# openSX70-dongle_v3-9.net
KiCad netlist of a schematic drawn in EAGLE
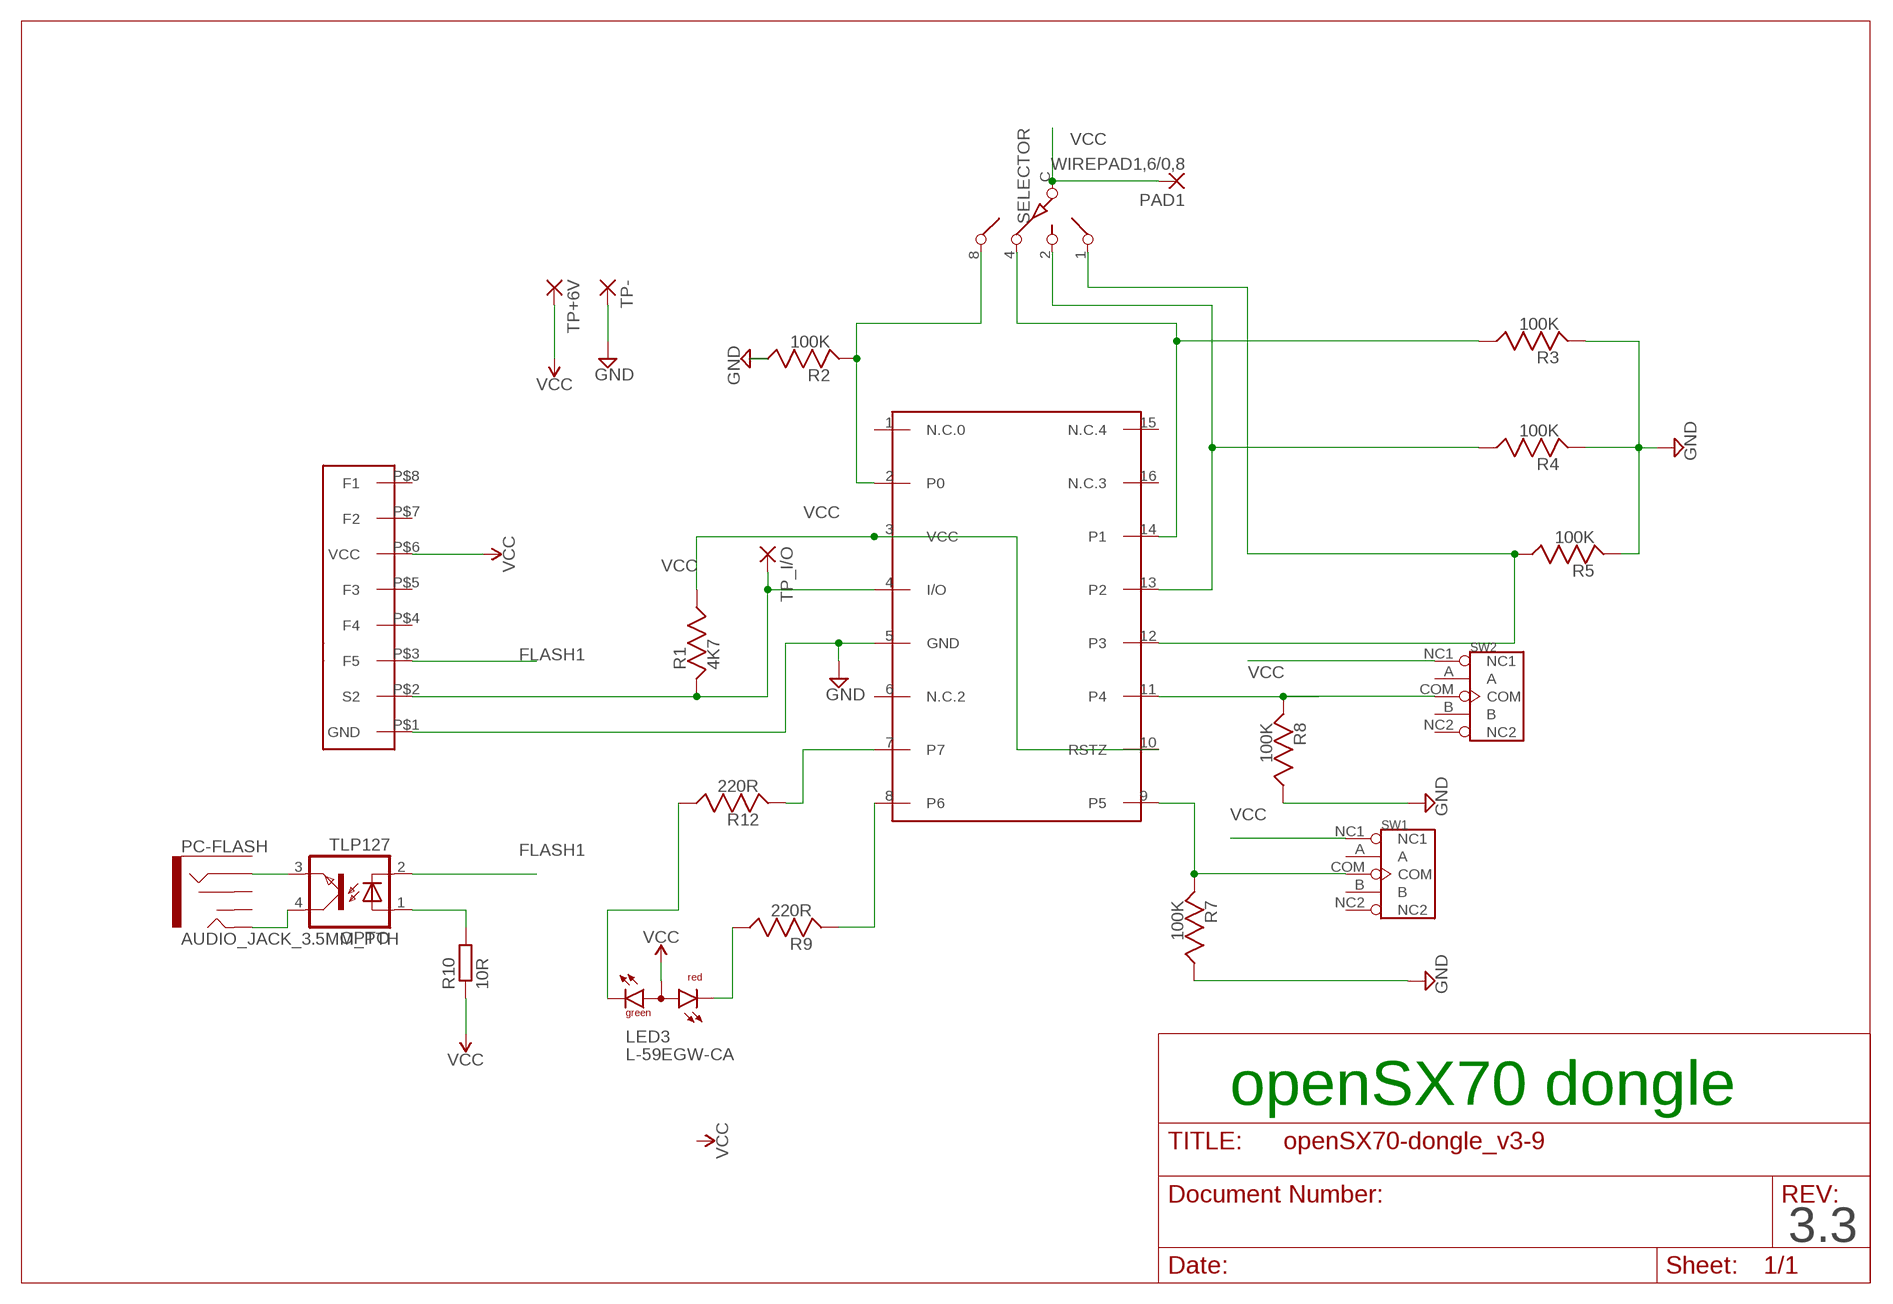
[diagram p0: schematic, sheet 1]

(export (version "E")
  (design (tool "Eeschema 10.0.6"))
  (components
    (comp (ref "DS2408")
      (value "DS2408")
      (footprint "eagle-import:SO16")
      (libsource (lib "eagle-import") (part "DS2408"))
    )
    (comp (ref "LED3")
      (value "L-59EGW-CA")
      (footprint "eagle-import:L-59EGW-CA")
      (libsource (lib "eagle-import") (part "L-59EGW-CA"))
    )
    (comp (ref "OPTO")
      (value "TLP127")
      (footprint "eagle-import:SO-4")
      (libsource (lib "eagle-import") (part "TLP127"))
    )
    (comp (ref "PAD1")
      (value "WIREPAD1,6/0,8")
      (footprint "eagle-import:1,6_0,8")
      (libsource (lib "eagle-import") (part "WIREPAD1,6/0,8"))
    )
    (comp (ref "PC-FLASH")
      (value "AUDIO_JACK_3.5MM_PTH")
      (footprint "eagle-import:AUDIO-JACK")
      (libsource (lib "eagle-import") (part "AUDIO_JACK_3.5MM_PTH"))
    )
    (comp (ref "R1")
      (value "4K7")
      (footprint "eagle-import:CRCW06034K70FKEA_RESC1608X55")
      (fields (field (name "MANUFACTURER") "VISHAY"))
      (libsource (lib "eagle-import") (part "CRCW06034K70FKEA"))
    )
    (comp (ref "R2")
      (value "100K")
      (footprint "eagle-import:ERJ-3EKF1003V_RESC1608X55")
      (fields (field (name "MANUFACTURER") "PANASONIC"))
      (libsource (lib "eagle-import") (part "ERJ-3EKF1003V"))
    )
    (comp (ref "R3")
      (value "100K")
      (footprint "eagle-import:ERJ-3EKF1003V_RESC1608X55")
      (fields (field (name "MANUFACTURER") "PANASONIC"))
      (libsource (lib "eagle-import") (part "ERJ-3EKF1003V"))
    )
    (comp (ref "R4")
      (value "100K")
      (footprint "eagle-import:ERJ-3EKF1003V_RESC1608X55")
      (fields (field (name "MANUFACTURER") "PANASONIC"))
      (libsource (lib "eagle-import") (part "ERJ-3EKF1003V"))
    )
    (comp (ref "R5")
      (value "100K")
      (footprint "eagle-import:ERJ-3EKF1003V_RESC1608X55")
      (fields (field (name "MANUFACTURER") "PANASONIC"))
      (libsource (lib "eagle-import") (part "ERJ-3EKF1003V"))
    )
    (comp (ref "R7")
      (value "100K")
      (footprint "eagle-import:ERJ-3EKF1003V_RESC1608X55")
      (fields (field (name "MANUFACTURER") "PANASONIC"))
      (libsource (lib "eagle-import") (part "ERJ-3EKF1003V"))
    )
    (comp (ref "R8")
      (value "100K")
      (footprint "eagle-import:ERJ-3EKF1003V_RESC1608X55")
      (fields (field (name "MANUFACTURER") "PANASONIC"))
      (libsource (lib "eagle-import") (part "ERJ-3EKF1003V"))
    )
    (comp (ref "R9")
      (value "220R")
      (footprint "eagle-import:RC0603FR-07220RL_RESC1608X55")
      (fields (field (name "MANUFACTURER") "YAGEO"))
      (libsource (lib "eagle-import") (part "RC0603FR-07220RL"))
    )
    (comp (ref "R10")
      (value "10R")
      (footprint "eagle-import:R0603")
      (libsource (lib "eagle-import") (part "R-EU_R0603"))
    )
    (comp (ref "R12")
      (value "220R")
      (footprint "eagle-import:RC0603FR-07220RL_RESC1608X55")
      (fields (field (name "MANUFACTURER") "YAGEO"))
      (libsource (lib "eagle-import") (part "RC0603FR-07220RL"))
    )
    (comp (ref "SELECTOR")
      (value "SW-C16")
      (footprint "eagle-import:SW-C16")
      (libsource (lib "eagle-import") (part "SW-C16"))
    )
    (comp (ref "SW1")
      (value "DIP-TOGGLE-SWITCH-ON-ON(3+2P-8.8X4.6MM)-90D")
      (footprint "eagle-import:SW5-2.0-8.8X4.4X4.7MM-90D")
      (fields (field (name "MPN") "3P-2.0-90D3P-2.0-90D-REINFORCE"))
      (libsource (lib "eagle-import") (part "DIP-TOGGLE-SWITCH-ON-ON(3+2P-8.8X4.6MM)-90D"))
    )
    (comp (ref "SW2")
      (value "DIP-TOGGLE-SWITCH-ON-ON(3+2P-8.8X4.6MM)-90D")
      (footprint "eagle-import:SW5-2.0-8.8X4.4X4.7MM-90D")
      (fields (field (name "MPN") "3P-2.0-90D3P-2.0-90D-REINFORCE"))
      (libsource (lib "eagle-import") (part "DIP-TOGGLE-SWITCH-ON-ON(3+2P-8.8X4.6MM)-90D"))
    )
    (comp (ref "TP+6V")
      (value "SMD2")
      (footprint "eagle-import:SMD1,27-2,54")
      (libsource (lib "eagle-import") (part "SMD2"))
    )
    (comp (ref "TP-")
      (value "SMD2")
      (footprint "eagle-import:SMD1,27-2,54")
      (libsource (lib "eagle-import") (part "SMD2"))
    )
    (comp (ref "TP_I/O")
      (value "SMD2")
      (footprint "eagle-import:SMD1,27-2,54")
      (libsource (lib "eagle-import") (part "SMD2"))
    )
    (comp (ref "U$1")
      (value "FLASH-EDGE-CONNECTOR")
      (footprint "eagle-import:FLASH-EDGE-8")
      (libsource (lib "eagle-import") (part "FLASH-EDGE-CONNECTOR"))
    )
  )
  (nets
    (net (code "1") (name "/FLASH1") (class "Default")
      (node (ref "OPTO") (pin "2") (pinfunction "C_2") (pintype "passive"))
      (node (ref "U$1") (pin "P$3") (pinfunction "F5_P$3") (pintype "bidirectional"))
    )
    (net (code "2") (name "GND") (class "Default")
      (node (ref "DS2408") (pin "5") (pinfunction "GND_5") (pintype "bidirectional"))
      (node (ref "R2") (pin "2") (pinfunction "2_2") (pintype "passive"))
      (node (ref "R3") (pin "1") (pinfunction "1_1") (pintype "passive"))
      (node (ref "R4") (pin "1") (pinfunction "1_1") (pintype "passive"))
      (node (ref "R5") (pin "1") (pinfunction "1_1") (pintype "passive"))
      (node (ref "R7") (pin "2") (pinfunction "2_2") (pintype "passive"))
      (node (ref "R8") (pin "2") (pinfunction "2_2") (pintype "passive"))
      (node (ref "TP-") (pin "1") (pinfunction "P_1") (pintype "passive"))
      (node (ref "U$1") (pin "P$1") (pinfunction "GND_P$1") (pintype "bidirectional"))
    )
    (net (code "3") (name "Net-(DS2408-I{slash}O)") (class "Default")
      (node (ref "DS2408") (pin "4") (pinfunction "I/O_4") (pintype "bidirectional"))
      (node (ref "R1") (pin "1") (pinfunction "1_1") (pintype "passive"))
      (node (ref "TP_I/O") (pin "1") (pinfunction "P_1") (pintype "passive"))
      (node (ref "U$1") (pin "P$2") (pinfunction "S2_P$2") (pintype "bidirectional"))
    )
    (net (code "4") (name "Net-(DS2408-P0)") (class "Default")
      (node (ref "DS2408") (pin "2") (pinfunction "P0_2") (pintype "bidirectional"))
      (node (ref "R2") (pin "1") (pinfunction "1_1") (pintype "passive"))
      (node (ref "SELECTOR") (pin "8") (pinfunction "8_8") (pintype "passive"))
    )
    (net (code "5") (name "Net-(DS2408-P1)") (class "Default")
      (node (ref "DS2408") (pin "14") (pinfunction "P1_14") (pintype "bidirectional"))
      (node (ref "R3") (pin "2") (pinfunction "2_2") (pintype "passive"))
      (node (ref "SELECTOR") (pin "4") (pinfunction "4_4") (pintype "passive"))
    )
    (net (code "6") (name "Net-(DS2408-P2)") (class "Default")
      (node (ref "DS2408") (pin "13") (pinfunction "P2_13") (pintype "bidirectional"))
      (node (ref "R4") (pin "2") (pinfunction "2_2") (pintype "passive"))
      (node (ref "SELECTOR") (pin "2") (pinfunction "2_2") (pintype "passive"))
    )
    (net (code "7") (name "Net-(DS2408-P3)") (class "Default")
      (node (ref "DS2408") (pin "12") (pinfunction "P3_12") (pintype "bidirectional"))
      (node (ref "R5") (pin "2") (pinfunction "2_2") (pintype "passive"))
      (node (ref "SELECTOR") (pin "1") (pinfunction "1_1") (pintype "passive"))
    )
    (net (code "8") (name "Net-(DS2408-P4)") (class "Default")
      (node (ref "DS2408") (pin "11") (pinfunction "P4_11") (pintype "bidirectional"))
      (node (ref "R8") (pin "1") (pinfunction "1_1") (pintype "passive"))
      (node (ref "SW2") (pin "COM") (pinfunction "COM_COM") (pintype "bidirectional"))
    )
    (net (code "9") (name "Net-(DS2408-P5)") (class "Default")
      (node (ref "DS2408") (pin "9") (pinfunction "P5_9") (pintype "bidirectional"))
      (node (ref "R7") (pin "1") (pinfunction "1_1") (pintype "passive"))
      (node (ref "SW1") (pin "COM") (pinfunction "COM_COM") (pintype "bidirectional"))
    )
    (net (code "10") (name "Net-(DS2408-P6)") (class "Default")
      (node (ref "DS2408") (pin "8") (pinfunction "P6_8") (pintype "bidirectional"))
      (node (ref "R9") (pin "1") (pinfunction "1_1") (pintype "passive"))
    )
    (net (code "11") (name "Net-(DS2408-P7)") (class "Default")
      (node (ref "DS2408") (pin "7") (pinfunction "P7_7") (pintype "bidirectional"))
      (node (ref "R12") (pin "1") (pinfunction "1_1") (pintype "passive"))
    )
    (net (code "12") (name "Net-(LED3-CG)") (class "Default")
      (node (ref "LED3") (pin "3") (pinfunction "CG_3") (pintype "passive"))
      (node (ref "R12") (pin "2") (pinfunction "2_2") (pintype "passive"))
    )
    (net (code "13") (name "Net-(LED3-CR)") (class "Default")
      (node (ref "LED3") (pin "1") (pinfunction "CR_1") (pintype "passive"))
      (node (ref "R9") (pin "2") (pinfunction "2_2") (pintype "passive"))
    )
    (net (code "14") (name "Net-(OPTO-A)") (class "Default")
      (node (ref "OPTO") (pin "1") (pinfunction "A_1") (pintype "passive"))
      (node (ref "R10") (pin "2") (pinfunction "2_2") (pintype "passive"))
    )
    (net (code "15") (name "Net-(OPTO-COL)") (class "Default")
      (node (ref "OPTO") (pin "4") (pinfunction "COL_4") (pintype "passive"))
      (node (ref "PC-FLASH") (pin "TIP") (pinfunction "TIP_TIP") (pintype "bidirectional"))
    )
    (net (code "16") (name "Net-(OPTO-EMIT)") (class "Default")
      (node (ref "OPTO") (pin "3") (pinfunction "EMIT_3") (pintype "passive"))
      (node (ref "PC-FLASH") (pin "RING") (pinfunction "RING_RING") (pintype "bidirectional"))
    )
    (net (code "17") (name "VCC") (class "Default")
      (node (ref "DS2408") (pin "10") (pinfunction "RSTZ_10") (pintype "bidirectional"))
      (node (ref "DS2408") (pin "3") (pinfunction "VCC_3") (pintype "bidirectional"))
      (node (ref "LED3") (pin "2") (pinfunction "A_2") (pintype "passive"))
      (node (ref "PAD1") (pin "1") (pinfunction "P_1") (pintype "passive"))
      (node (ref "R1") (pin "2") (pinfunction "2_2") (pintype "passive"))
      (node (ref "R10") (pin "1") (pinfunction "1_1") (pintype "passive"))
      (node (ref "SELECTOR") (pin "C") (pinfunction "C_C") (pintype "passive"))
      (node (ref "SW1") (pin "NC1") (pinfunction "NC1_NC1") (pintype "bidirectional"))
      (node (ref "SW2") (pin "NC1") (pinfunction "NC1_NC1") (pintype "bidirectional"))
      (node (ref "TP+6V") (pin "1") (pinfunction "P_1") (pintype "passive"))
      (node (ref "U$1") (pin "P$6") (pinfunction "VCC_P$6") (pintype "bidirectional"))
    )
    (net (code "18") (name "unconnected-(DS2408-N.C.0-Pad1)") (class "Default")
      (node (ref "DS2408") (pin "1") (pinfunction "N.C.0_1") (pintype "bidirectional"))
    )
    (net (code "19") (name "unconnected-(DS2408-N.C.2-Pad6)") (class "Default")
      (node (ref "DS2408") (pin "6") (pinfunction "N.C.2_6") (pintype "bidirectional"))
    )
    (net (code "20") (name "unconnected-(DS2408-N.C.3-Pad16)") (class "Default")
      (node (ref "DS2408") (pin "16") (pinfunction "N.C.3_16") (pintype "bidirectional"))
    )
    (net (code "21") (name "unconnected-(DS2408-N.C.4-Pad15)") (class "Default")
      (node (ref "DS2408") (pin "15") (pinfunction "N.C.4_15") (pintype "bidirectional"))
    )
    (net (code "22") (name "unconnected-(PC-FLASH-PadRSH)") (class "Default")
      (node (ref "PC-FLASH") (pin "RSH") (pinfunction "RSH_RSH") (pintype "bidirectional"))
    )
    (net (code "23") (name "unconnected-(PC-FLASH-PadSLEEVE)") (class "Default")
      (node (ref "PC-FLASH") (pin "SLEEVE") (pinfunction "SLEEVE_SLEEVE") (pintype "bidirectional"))
    )
    (net (code "24") (name "unconnected-(PC-FLASH-PadTSH)") (class "Default")
      (node (ref "PC-FLASH") (pin "TSH") (pinfunction "TSH_TSH") (pintype "bidirectional"))
    )
    (net (code "25") (name "unconnected-(SW1-PadA)") (class "Default")
      (node (ref "SW1") (pin "A") (pinfunction "A_A") (pintype "bidirectional"))
    )
    (net (code "26") (name "unconnected-(SW1-PadB)") (class "Default")
      (node (ref "SW1") (pin "B") (pinfunction "B_B") (pintype "bidirectional"))
    )
    (net (code "27") (name "unconnected-(SW1-PadNC2)") (class "Default")
      (node (ref "SW1") (pin "NC2") (pinfunction "NC2_NC2") (pintype "bidirectional"))
    )
    (net (code "28") (name "unconnected-(SW2-PadA)") (class "Default")
      (node (ref "SW2") (pin "A") (pinfunction "A_A") (pintype "bidirectional"))
    )
    (net (code "29") (name "unconnected-(SW2-PadB)") (class "Default")
      (node (ref "SW2") (pin "B") (pinfunction "B_B") (pintype "bidirectional"))
    )
    (net (code "30") (name "unconnected-(SW2-PadNC2)") (class "Default")
      (node (ref "SW2") (pin "NC2") (pinfunction "NC2_NC2") (pintype "bidirectional"))
    )
    (net (code "31") (name "unconnected-(U$1-F1-PadP$8)") (class "Default")
      (node (ref "U$1") (pin "P$8") (pinfunction "F1_P$8") (pintype "bidirectional"))
    )
    (net (code "32") (name "unconnected-(U$1-F2-PadP$7)") (class "Default")
      (node (ref "U$1") (pin "P$7") (pinfunction "F2_P$7") (pintype "bidirectional"))
    )
    (net (code "33") (name "unconnected-(U$1-F3-PadP$5)") (class "Default")
      (node (ref "U$1") (pin "P$5") (pinfunction "F3_P$5") (pintype "bidirectional"))
    )
    (net (code "34") (name "unconnected-(U$1-F4-PadP$4)") (class "Default")
      (node (ref "U$1") (pin "P$4") (pinfunction "F4_P$4") (pintype "bidirectional"))
    )
  )
)
